# LCDTFT_FPC40P_LVDS.net
KiCad netlist of a schematic drawn in Altium Designer
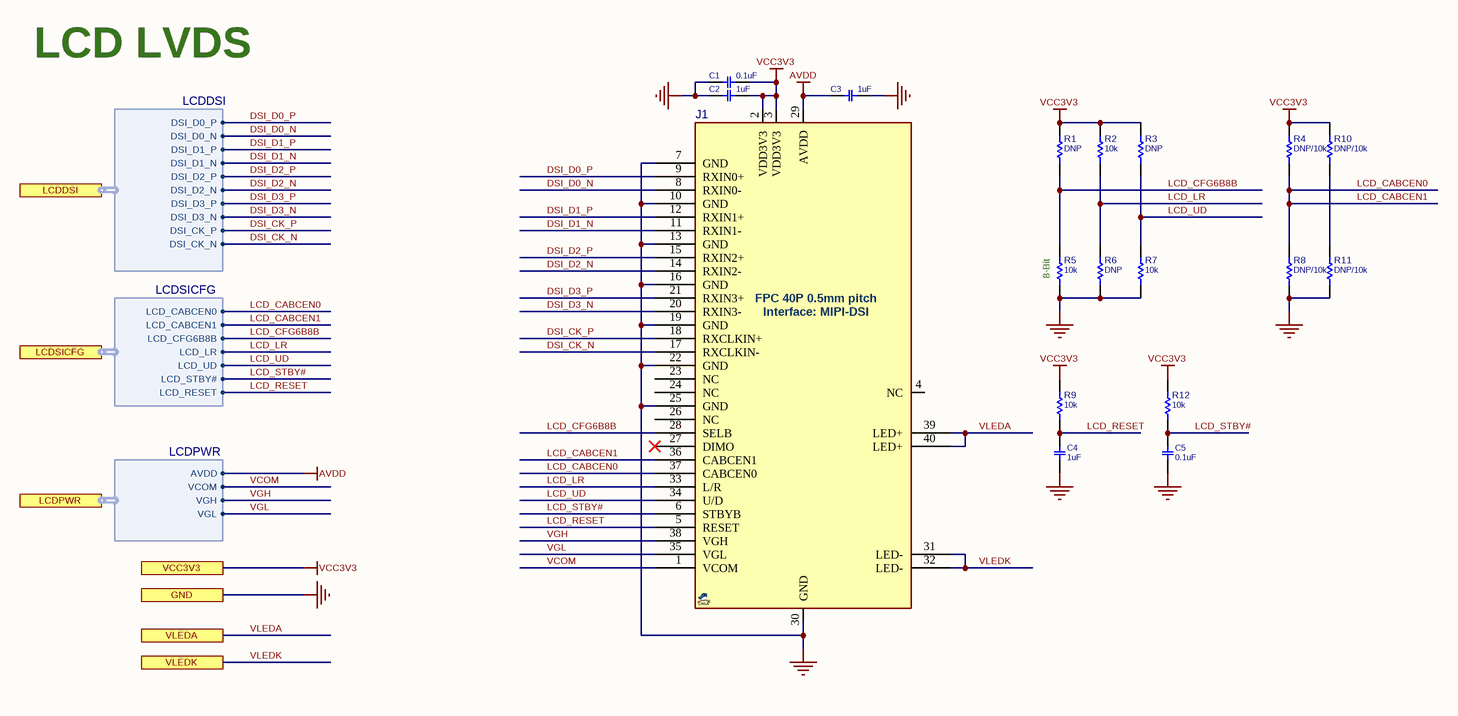
[diagram p0: LCDTFT_FPC40P_LVDS.SchDoc]

(export (version "E")
  (design (tool "Eeschema 10.0.6"))
  (components
    (comp (ref "C1")
      (value "0.1uF")
      (footprint "C0402")
      (description "CAP, MLCC")
      (fields (field (name "MANF_P#") "GRM155R71H104KE14D") (field (name "MANF") "Murata"))
      (libsource (lib "passive_smd") (part "CAP_SMD_MLCC"))
    )
    (comp (ref "C2")
      (value "1uF")
      (footprint "C0402")
      (description "CAP, MLCC")
      (fields (field (name "MANF_P#") "CL05A105KO5NNND") (field (name "MANF") "Samsung"))
      (libsource (lib "passive_smd") (part "CAP_SMD_MLCC"))
    )
    (comp (ref "C3")
      (value "1uF")
      (footprint "C0402")
      (description "CAP, MLCC")
      (fields (field (name "MANF_P#") "CL05A105KO5NNND") (field (name "MANF") "Samsung"))
      (libsource (lib "passive_smd") (part "CAP_SMD_MLCC"))
    )
    (comp (ref "C4")
      (value "1uF")
      (footprint "C0402")
      (description "CAP, MLCC")
      (fields (field (name "MANF_P#") "CL05A105KO5NNND") (field (name "MANF") "Samsung"))
      (libsource (lib "passive_smd") (part "CAP_SMD_MLCC"))
    )
    (comp (ref "C5")
      (value "0.1uF")
      (footprint "C0402")
      (description "CAP, MLCC")
      (fields (field (name "MANF_P#") "GRM155R71H104KE14D") (field (name "MANF") "Murata"))
      (libsource (lib "passive_smd") (part "CAP_SMD_MLCC"))
    )
    (comp (ref "J1")
      (value "FPC_40_0.5mm")
      (footprint "FPC50_40")
      (description "LCD TFT Color, FPC40P, LVDS")
      (libsource (lib "lcdtft") (part "LCDTFT_DSI_FPC40P"))
    )
    (comp (ref "R1")
      (value "DNP")
      (footprint "R0402")
      (description "RESISTOR, SMD")
      (libsource (lib "passive_res_smd") (part "RES_SMD"))
    )
    (comp (ref "R2")
      (value "10k")
      (footprint "R0402")
      (description "RESISTOR, SMD")
      (libsource (lib "passive_res_smd") (part "RES_SMD"))
    )
    (comp (ref "R3")
      (value "DNP")
      (footprint "R0402")
      (description "RESISTOR, SMD")
      (libsource (lib "passive_res_smd") (part "RES_SMD"))
    )
    (comp (ref "R4")
      (value "DNP/10k")
      (footprint "R0402")
      (description "RESISTOR, SMD")
      (libsource (lib "passive_res_smd") (part "RES_SMD"))
    )
    (comp (ref "R5")
      (value "10k")
      (footprint "R0402")
      (description "RESISTOR, SMD")
      (libsource (lib "passive_res_smd") (part "RES_SMD"))
    )
    (comp (ref "R6")
      (value "DNP")
      (footprint "R0402")
      (description "RESISTOR, SMD")
      (libsource (lib "passive_res_smd") (part "RES_SMD"))
    )
    (comp (ref "R7")
      (value "10k")
      (footprint "R0402")
      (description "RESISTOR, SMD")
      (libsource (lib "passive_res_smd") (part "RES_SMD"))
    )
    (comp (ref "R8")
      (value "DNP/10k")
      (footprint "R0402")
      (description "RESISTOR, SMD")
      (libsource (lib "passive_res_smd") (part "RES_SMD"))
    )
    (comp (ref "R9")
      (value "10k")
      (footprint "R0402")
      (description "RESISTOR, SMD")
      (libsource (lib "passive_res_smd") (part "RES_SMD"))
    )
    (comp (ref "R10")
      (value "DNP/10k")
      (footprint "R0402")
      (description "RESISTOR, SMD")
      (libsource (lib "passive_res_smd") (part "RES_SMD"))
    )
    (comp (ref "R11")
      (value "DNP/10k")
      (footprint "R0402")
      (description "RESISTOR, SMD")
      (libsource (lib "passive_res_smd") (part "RES_SMD"))
    )
    (comp (ref "R12")
      (value "10k")
      (footprint "R0402")
      (description "RESISTOR, SMD")
      (libsource (lib "passive_res_smd") (part "RES_SMD"))
    )
  )
  (nets
    (net (code "4") (name "/DSI_CK_N") (class "Default")
      (node (ref "J1") (pin "17") (pinfunction "RXCLKIN-_17") (pintype "passive"))
    )
    (net (code "5") (name "/DSI_CK_P") (class "Default")
      (node (ref "J1") (pin "18") (pinfunction "RXCLKIN+_18") (pintype "passive"))
    )
    (net (code "6") (name "/DSI_D0_N") (class "Default")
      (node (ref "J1") (pin "8") (pinfunction "RXIN0-_8") (pintype "passive"))
    )
    (net (code "7") (name "/DSI_D0_P") (class "Default")
      (node (ref "J1") (pin "9") (pinfunction "RXIN0+_9") (pintype "passive"))
    )
    (net (code "8") (name "/DSI_D1_N") (class "Default")
      (node (ref "J1") (pin "11") (pinfunction "RXIN1-_11") (pintype "passive"))
    )
    (net (code "9") (name "/DSI_D1_P") (class "Default")
      (node (ref "J1") (pin "12") (pinfunction "RXIN1+_12") (pintype "passive"))
    )
    (net (code "10") (name "/DSI_D2_N") (class "Default")
      (node (ref "J1") (pin "14") (pinfunction "RXIN2-_14") (pintype "passive"))
    )
    (net (code "11") (name "/DSI_D2_P") (class "Default")
      (node (ref "J1") (pin "15") (pinfunction "RXIN2+_15") (pintype "passive"))
    )
    (net (code "12") (name "/DSI_D3_N") (class "Default")
      (node (ref "J1") (pin "20") (pinfunction "RXIN3-_20") (pintype "passive"))
    )
    (net (code "13") (name "/DSI_D3_P") (class "Default")
      (node (ref "J1") (pin "21") (pinfunction "RXIN3+_21") (pintype "passive"))
    )
    (net (code "14") (name "/LCD_CABCEN0") (class "Default")
      (node (ref "J1") (pin "36") (pinfunction "CABCEN1_36") (pintype "passive"))
      (node (ref "J1") (pin "37") (pinfunction "CABCEN0_37") (pintype "passive"))
      (node (ref "R4") (pin "2") (pinfunction "2_2") (pintype "passive"))
      (node (ref "R8") (pin "1") (pinfunction "1_1") (pintype "passive"))
    )
    (net (code "15") (name "/LCD_CFG6B8B") (class "Default")
      (node (ref "J1") (pin "28") (pinfunction "SELB_28") (pintype "passive"))
      (node (ref "R1") (pin "2") (pinfunction "2_2") (pintype "passive"))
      (node (ref "R5") (pin "1") (pinfunction "1_1") (pintype "passive"))
    )
    (net (code "16") (name "/LCD_LR") (class "Default")
      (node (ref "J1") (pin "33") (pinfunction "L/R_33") (pintype "passive"))
      (node (ref "R2") (pin "2") (pinfunction "2_2") (pintype "passive"))
      (node (ref "R6") (pin "1") (pinfunction "1_1") (pintype "passive"))
    )
    (net (code "17") (name "/LCD_RESET") (class "Default")
      (node (ref "C4") (pin "1") (pinfunction "1_1") (pintype "passive"))
      (node (ref "J1") (pin "5") (pinfunction "RESET_5") (pintype "passive"))
      (node (ref "R9") (pin "2") (pinfunction "2_2") (pintype "passive"))
    )
    (net (code "18") (name "/LCD_STBY#") (class "Default")
      (node (ref "C5") (pin "1") (pinfunction "1_1") (pintype "passive"))
      (node (ref "J1") (pin "6") (pinfunction "STBYB_6") (pintype "passive"))
      (node (ref "R12") (pin "2") (pinfunction "2_2") (pintype "passive"))
    )
    (net (code "19") (name "/LCD_UD") (class "Default")
      (node (ref "J1") (pin "34") (pinfunction "U/D_34") (pintype "passive"))
      (node (ref "R3") (pin "2") (pinfunction "2_2") (pintype "passive"))
      (node (ref "R7") (pin "1") (pinfunction "1_1") (pintype "passive"))
    )
    (net (code "20") (name "/VCOM") (class "Default")
      (node (ref "J1") (pin "1") (pinfunction "VCOM_1") (pintype "passive"))
    )
    (net (code "21") (name "/VGH") (class "Default")
      (node (ref "J1") (pin "38") (pinfunction "VGH_38") (pintype "passive"))
    )
    (net (code "22") (name "/VGL") (class "Default")
      (node (ref "J1") (pin "35") (pinfunction "VGL_35") (pintype "passive"))
    )
    (net (code "23") (name "/VLEDA") (class "Default")
      (node (ref "J1") (pin "39") (pinfunction "LED+_39") (pintype "passive"))
      (node (ref "J1") (pin "40") (pinfunction "LED+_40") (pintype "passive"))
    )
    (net (code "24") (name "/VLEDK") (class "Default")
      (node (ref "J1") (pin "31") (pinfunction "LED-_31") (pintype "passive"))
      (node (ref "J1") (pin "32") (pinfunction "LED-_32") (pintype "passive"))
    )
    (net (code "28") (name "AVDD") (class "Default")
      (node (ref "C3") (pin "2") (pinfunction "2_2") (pintype "passive"))
      (node (ref "J1") (pin "29") (pinfunction "AVDD_29") (pintype "passive"))
    )
    (net (code "29") (name "GND") (class "Default")
      (node (ref "C1") (pin "2") (pinfunction "2_2") (pintype "passive"))
      (node (ref "C2") (pin "2") (pinfunction "2_2") (pintype "passive"))
      (node (ref "C3") (pin "1") (pinfunction "1_1") (pintype "passive"))
      (node (ref "C4") (pin "2") (pinfunction "2_2") (pintype "passive"))
      (node (ref "C5") (pin "2") (pinfunction "2_2") (pintype "passive"))
      (node (ref "J1") (pin "10") (pinfunction "GND_10") (pintype "passive"))
      (node (ref "J1") (pin "13") (pinfunction "GND_13") (pintype "passive"))
      (node (ref "J1") (pin "16") (pinfunction "GND_16") (pintype "passive"))
      (node (ref "J1") (pin "19") (pinfunction "GND_19") (pintype "passive"))
      (node (ref "J1") (pin "22") (pinfunction "GND_22") (pintype "passive"))
      (node (ref "J1") (pin "25") (pinfunction "GND_25") (pintype "passive"))
      (node (ref "J1") (pin "30") (pinfunction "GND_30") (pintype "passive"))
      (node (ref "J1") (pin "7") (pinfunction "GND_7") (pintype "passive"))
      (node (ref "R11") (pin "2") (pinfunction "2_2") (pintype "passive"))
      (node (ref "R5") (pin "2") (pinfunction "2_2") (pintype "passive"))
      (node (ref "R6") (pin "2") (pinfunction "2_2") (pintype "passive"))
      (node (ref "R7") (pin "2") (pinfunction "2_2") (pintype "passive"))
      (node (ref "R8") (pin "2") (pinfunction "2_2") (pintype "passive"))
    )
    (net (code "30") (name "Net-(R10-Pad2)") (class "Default")
      (node (ref "R10") (pin "2") (pinfunction "2_2") (pintype "passive"))
      (node (ref "R11") (pin "1") (pinfunction "1_1") (pintype "passive"))
    )
    (net (code "31") (name "VCC3V3") (class "Default")
      (node (ref "C1") (pin "1") (pinfunction "1_1") (pintype "passive"))
      (node (ref "C2") (pin "1") (pinfunction "1_1") (pintype "passive"))
      (node (ref "J1") (pin "2") (pinfunction "VDD3V3_2") (pintype "passive"))
      (node (ref "J1") (pin "3") (pinfunction "VDD3V3_3") (pintype "passive"))
      (node (ref "R1") (pin "1") (pinfunction "1_1") (pintype "passive"))
      (node (ref "R10") (pin "1") (pinfunction "1_1") (pintype "passive"))
      (node (ref "R12") (pin "1") (pinfunction "1_1") (pintype "passive"))
      (node (ref "R2") (pin "1") (pinfunction "1_1") (pintype "passive"))
      (node (ref "R3") (pin "1") (pinfunction "1_1") (pintype "passive"))
      (node (ref "R4") (pin "1") (pinfunction "1_1") (pintype "passive"))
      (node (ref "R9") (pin "1") (pinfunction "1_1") (pintype "passive"))
    )
    (net (code "32") (name "unconnected-(J1-DIMO-Pad27)") (class "Default")
      (node (ref "J1") (pin "27") (pinfunction "DIMO_27") (pintype "passive+no_connect"))
    )
    (net (code "33") (name "unconnected-(J1-NC-Pad4)") (class "Default")
      (node (ref "J1") (pin "4") (pinfunction "NC_4") (pintype "passive"))
    )
    (net (code "34") (name "unconnected-(J1-NC-Pad23)") (class "Default")
      (node (ref "J1") (pin "23") (pinfunction "NC_23") (pintype "passive"))
    )
    (net (code "35") (name "unconnected-(J1-NC-Pad24)") (class "Default")
      (node (ref "J1") (pin "24") (pinfunction "NC_24") (pintype "passive"))
    )
    (net (code "36") (name "unconnected-(J1-NC-Pad26)") (class "Default")
      (node (ref "J1") (pin "26") (pinfunction "NC_26") (pintype "passive"))
    )
  )
)
